# canbus.net
KiCad netlist of a schematic drawn in Altium Designer
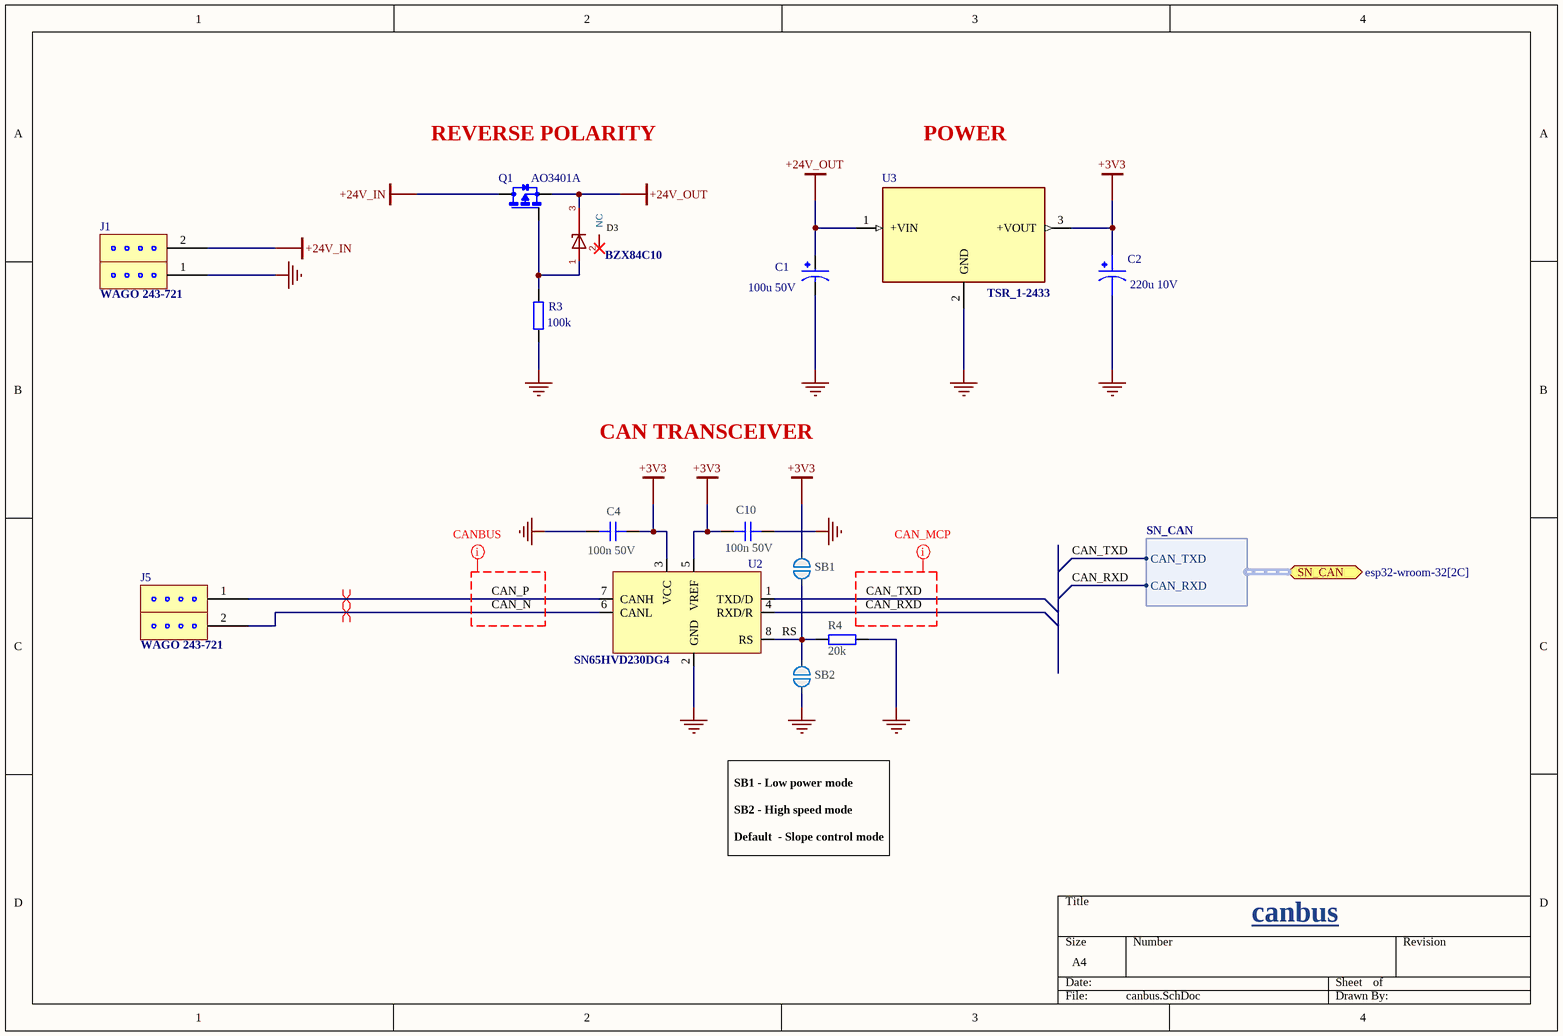
[diagram p0: canbus.SchDoc]

(export (version "E")
  (design (tool "Eeschema 10.0.6"))
  (components
    (comp (ref "C1")
      (value "100u 50V")
      (footprint "Fp_Lib:CAPPRD500W60D800H1150")
      (description "100F 50V Aluminum Electrolytic Capacitors Radial, Can 1000 Hrs @ 105C")
      (fields (field (name "MP") "ECA-1HHG101B") (field (name "MF") "Panasonic Electronic"))
      (libsource (lib "Sch_Lib") (part "ECA1HHG101B"))
    )
    (comp (ref "C2")
      (value "220u 10V")
      (footprint "CAPPM7343X310N")
      (description "220 ÂµF Molded Tantalum Capacitors 10 V 2917 (7343 Metric) 50mOhm")
      (fields (field (name "MF") "AVX") (field (name "MP") "TPSD227M010R0050"))
      (libsource (lib "Sch_Lib") (part "TPSD227M010R0050"))
    )
    (comp (ref "C4")
      (value "100n 50V")
      (footprint "CAPC1005X04L")
      (description "Capacitor, X5R, ±20%")
      (fields
        (field (name "PART NUMBER") "C0402-4µ7")
        (field (name "MANUFACTURER") "N.A.")
        (field (name "AUTHOR") "rsk")
      )
      (libsource (lib "Sch_Lib") (part "C0402-4µ7"))
    )
    (comp (ref "C10")
      (value "100n 50V")
      (footprint "CAPC1005X04L")
      (description "Capacitor, X5R, ±20%")
      (fields
        (field (name "PART NUMBER") "C0402-4µ7")
        (field (name "MANUFACTURER") "N.A.")
        (field (name "AUTHOR") "rsk")
      )
      (libsource (lib "Sch_Lib") (part "C0402-4µ7"))
    )
    (comp (ref "D3") (value "BZX84C10") (footprint "SOT-23") (libsource (lib "Sch_Lib") (part "BZX84C10")))
    (comp (ref "J1")
      (value "WAGO 243-721")
      (footprint "243-721")
      (description "TERM BLOCK PLUG 1POS 5.75MM")
      (libsource (lib "") (part "243-721_1"))
    )
    (comp (ref "J5")
      (value "WAGO 243-721")
      (footprint "243-721")
      (description "TERM BLOCK PLUG 1POS 5.75MM")
      (libsource (lib "Sch_Lib") (part "243-721"))
    )
    (comp (ref "Q1")
      (value "AO3401A")
      (footprint "SOT23")
      (description "P-Channel 30 V 4A (Ta) 1.4W (Ta) Surface Mount SOT-23-3")
      (fields (field (name "MF") "Alpha & Omega Semiconductor"))
      (libsource (lib "Sch_Lib") (part "AO3401A"))
    )
    (comp (ref "R3")
      (value "100k")
      (footprint "RES_0603")
      (description "Resistor SMD 0603")
      (libsource (lib "Sch_Lib") (part "RES_0603"))
    )
    (comp (ref "R4")
      (value "20k")
      (footprint "RESC1005X04L")
      (description "Resistor, ±5%, 0.063W")
      (fields
        (field (name "PART NUMBER") "R0402-0R")
        (field (name "MANUFACTURER") "N.A.")
        (field (name "AUTHOR") "rsk")
      )
      (libsource (lib "Sch_Lib") (part "R0402-0R"))
    )
    (comp (ref "SB1")
      (value "Solderbridge")
      (footprint "Solderbridge")
      (fields (field (name "MANUFACTURER") "N.A.") (field (name "AUTHOR") "rsk"))
      (libsource (lib "Sch_Lib") (part "Solderbridge"))
    )
    (comp (ref "SB2")
      (value "Solderbridge")
      (footprint "Solderbridge")
      (fields (field (name "MANUFACTURER") "N.A.") (field (name "AUTHOR") "rsk"))
      (libsource (lib "Sch_Lib") (part "Solderbridge"))
    )
    (comp (ref "U2")
      (value "SN65HVD230DG4")
      (footprint "SOIC127P599X175-8N")
      (description "3.3 V CAN Transceiver with Standby Mode 8-SOIC -40 to 85")
      (fields (field (name "MF") "Texas Instruments"))
      (libsource (lib "Sch_Lib") (part "SN65HVD230DG4"))
    )
    (comp (ref "U3")
      (value "TSR_1-2433")
      (footprint "Fp_Lib:TSR-1")
      (description "1 Amp POL switching regulator, 4.6 to -36 VDC input, pos.-pos. circuit, LM78 compatible, SIP-3")
      (fields (field (name "MP") "TSR 1-2433") (field (name "MF") "Traco Power"))
      (libsource (lib "Sch_Lib") (part "TSR_1-2433"))
    )
  )
  (nets
    (net (code "2") (name "+3V3") (class "Default")
      (node (ref "C10") (pin "1") (pinfunction "1_1") (pintype "passive"))
      (node (ref "C2") (pin "1") (pinfunction "1_1") (pintype "passive"))
      (node (ref "C4") (pin "2") (pinfunction "2_2") (pintype "passive"))
      (node (ref "SB1") (pin "1") (pinfunction "0_1") (pintype "passive"))
      (node (ref "U2") (pin "3") (pinfunction "VCC_3") (pintype "passive"))
      (node (ref "U2") (pin "5") (pinfunction "VREF_5") (pintype "passive"))
      (node (ref "U3") (pin "3") (pinfunction "+VOUT_3") (pintype "output"))
    )
    (net (code "3") (name "+24V_IN") (class "Default")
      (node (ref "J1") (pin "2") (pinfunction "2_2") (pintype "passive"))
      (node (ref "Q1") (pin "3") (pinfunction "D_3") (pintype "passive"))
    )
    (net (code "4") (name "+24V_OUT") (class "Default")
      (node (ref "C1") (pin "P") (pinfunction "P_P") (pintype "passive"))
      (node (ref "D3") (pin "3") (pinfunction "C_3") (pintype "passive"))
      (node (ref "Q1") (pin "2") (pinfunction "S_2") (pintype "passive"))
      (node (ref "U3") (pin "1") (pinfunction "+VIN_1") (pintype "input"))
    )
    (net (code "5") (name "/CAN_N") (class "Default")
      (node (ref "J5") (pin "2") (pinfunction "2_2") (pintype "passive"))
      (node (ref "U2") (pin "6") (pinfunction "CANL_6") (pintype "passive"))
    )
    (net (code "6") (name "/CAN_P") (class "Default")
      (node (ref "J5") (pin "1") (pinfunction "1_1") (pintype "passive"))
      (node (ref "U2") (pin "7") (pinfunction "CANH_7") (pintype "passive"))
    )
    (net (code "7") (name "/CAN_RXD") (class "Default")
      (node (ref "U2") (pin "4") (pinfunction "RXD/R_4") (pintype "passive"))
    )
    (net (code "8") (name "/CAN_TXD") (class "Default")
      (node (ref "U2") (pin "1") (pinfunction "TXD/D_1") (pintype "passive"))
    )
    (net (code "9") (name "/RS") (class "Default")
      (node (ref "R4") (pin "1") (pinfunction "1_1") (pintype "passive"))
      (node (ref "SB1") (pin "2") (pinfunction "1_2") (pintype "passive"))
      (node (ref "SB2") (pin "1") (pinfunction "0_1") (pintype "passive"))
      (node (ref "U2") (pin "8") (pinfunction "RS_8") (pintype "passive"))
    )
    (net (code "11") (name "GND") (class "Default")
      (node (ref "C1") (pin "N") (pinfunction "N_N") (pintype "passive"))
      (node (ref "C10") (pin "2") (pinfunction "2_2") (pintype "passive"))
      (node (ref "C2") (pin "2") (pinfunction "2_2") (pintype "passive"))
      (node (ref "C4") (pin "1") (pinfunction "1_1") (pintype "passive"))
      (node (ref "J1") (pin "1") (pinfunction "1_1") (pintype "passive"))
      (node (ref "R3") (pin "1") (pinfunction "1_1") (pintype "passive"))
      (node (ref "R4") (pin "2") (pinfunction "2_2") (pintype "passive"))
      (node (ref "SB2") (pin "2") (pinfunction "1_2") (pintype "passive"))
      (node (ref "U2") (pin "2") (pinfunction "GND_2") (pintype "passive"))
      (node (ref "U3") (pin "2") (pinfunction "GND_2") (pintype "power_in"))
    )
    (net (code "12") (name "Net-(D3-A)") (class "Default")
      (node (ref "D3") (pin "1") (pinfunction "A_1") (pintype "passive"))
      (node (ref "Q1") (pin "1") (pinfunction "G_1") (pintype "passive"))
      (node (ref "R3") (pin "2") (pinfunction "2_2") (pintype "passive"))
    )
    (net (code "13") (name "unconnected-(D3-NC-Pad2)") (class "Default")
      (node (ref "D3") (pin "2") (pinfunction "NC_2") (pintype "passive+no_connect"))
    )
  )
)
